# PCB_Mega.net
KiCad netlist of a schematic drawn in EAGLE
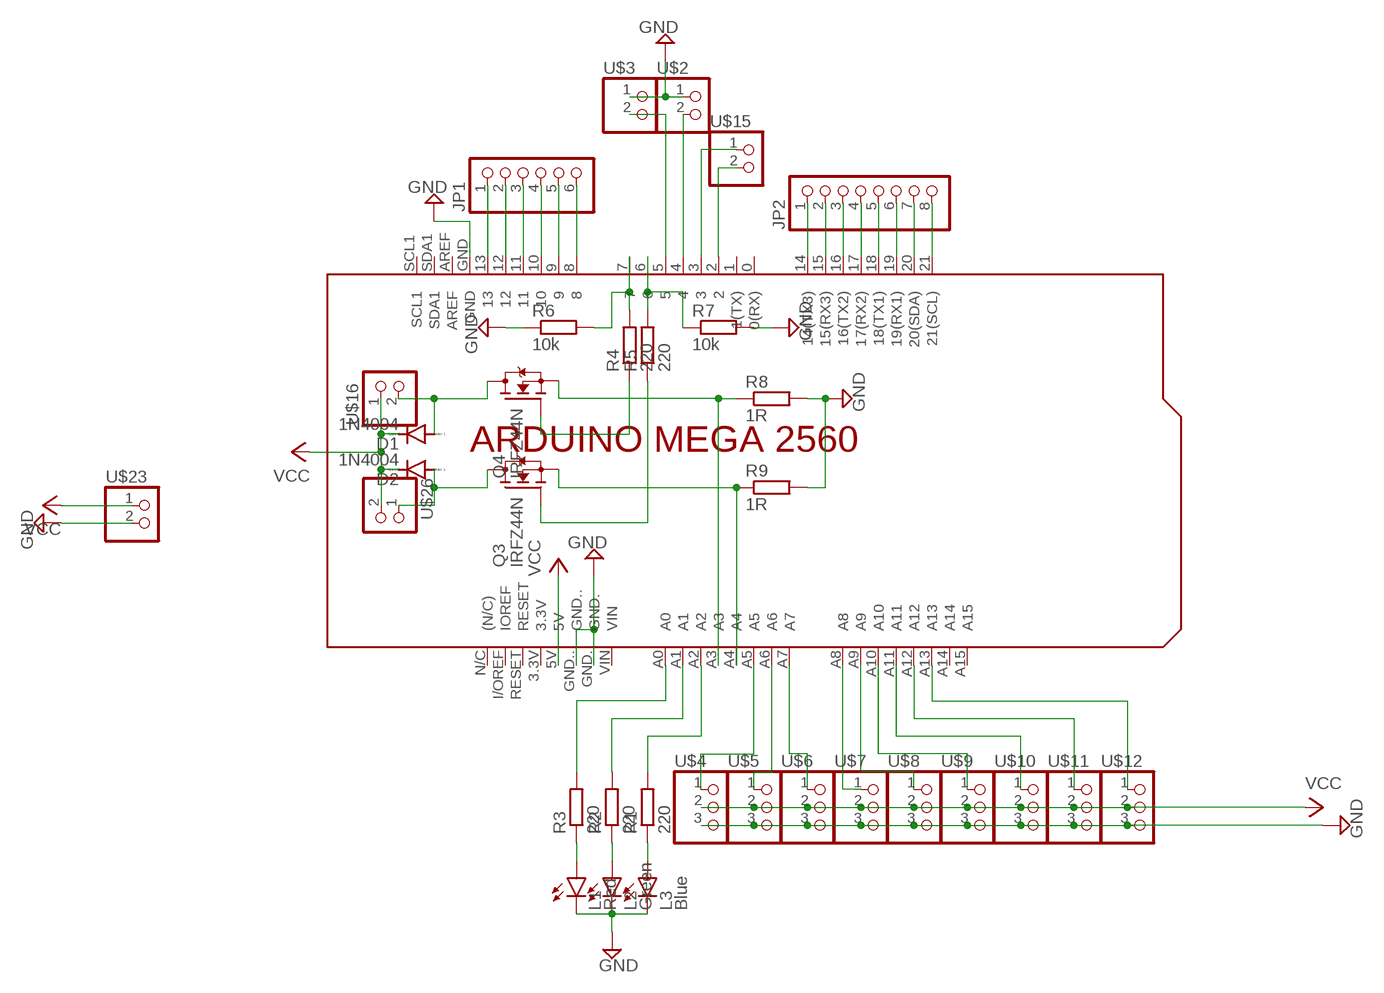
[diagram p0: schematic, sheet 1]

(export (version "E")
  (design (tool "Eeschema 10.0.6"))
  (components
    (comp (ref "D1")
      (value "1N4004")
      (footprint "eagle-import:DO41-10")
      (libsource (lib "eagle-import") (part "1N4004"))
    )
    (comp (ref "D2")
      (value "1N4004")
      (footprint "eagle-import:DO41-10")
      (libsource (lib "eagle-import") (part "1N4004"))
    )
    (comp (ref "JP1")
      (value "PINHD-1X6")
      (footprint "eagle-import:1X06")
      (libsource (lib "eagle-import") (part "PINHD-1X6"))
    )
    (comp (ref "JP2")
      (value "PINHD-1X8")
      (footprint "eagle-import:1X08")
      (libsource (lib "eagle-import") (part "PINHD-1X8"))
    )
    (comp (ref "L1")
      (value "Red")
      (footprint "eagle-import:LED3MM")
      (libsource (lib "eagle-import") (part "LED3MM"))
    )
    (comp (ref "L2")
      (value "Green")
      (footprint "eagle-import:LED3MM")
      (libsource (lib "eagle-import") (part "LED3MM"))
    )
    (comp (ref "L3")
      (value "Blue")
      (footprint "eagle-import:LED3MM")
      (libsource (lib "eagle-import") (part "LED3MM"))
    )
    (comp (ref "Q3")
      (value "IRFZ44N")
      (footprint "eagle-import:TO220V")
      (libsource (lib "eagle-import") (part "IRFZ44N"))
    )
    (comp (ref "Q4")
      (value "IRFZ44N")
      (footprint "eagle-import:TO220V")
      (libsource (lib "eagle-import") (part "IRFZ44N"))
    )
    (comp (ref "R1")
      (value "220")
      (footprint "eagle-import:0207_7-OFFSET")
      (libsource (lib "eagle-import") (part "RESISTOR_1/4WOFFSET"))
    )
    (comp (ref "R2")
      (value "220")
      (footprint "eagle-import:0207_7-OFFSET")
      (libsource (lib "eagle-import") (part "RESISTOR_1/4WOFFSET"))
    )
    (comp (ref "R3")
      (value "220")
      (footprint "eagle-import:0207_7-OFFSET")
      (libsource (lib "eagle-import") (part "RESISTOR_1/4WOFFSET"))
    )
    (comp (ref "R4")
      (value "220")
      (footprint "eagle-import:0207_7-OFFSET")
      (libsource (lib "eagle-import") (part "RESISTOR_1/4WOFFSET"))
    )
    (comp (ref "R5")
      (value "220")
      (footprint "eagle-import:0207_7-OFFSET")
      (libsource (lib "eagle-import") (part "RESISTOR_1/4WOFFSET"))
    )
    (comp (ref "R6")
      (value "10k")
      (footprint "eagle-import:0207_7-OFFSET")
      (libsource (lib "eagle-import") (part "RESISTOR_1/4WOFFSET"))
    )
    (comp (ref "R7")
      (value "10k")
      (footprint "eagle-import:0207_7-OFFSET")
      (libsource (lib "eagle-import") (part "RESISTOR_1/4WOFFSET"))
    )
    (comp (ref "R8")
      (value "1R")
      (footprint "eagle-import:10_28-90")
      (libsource (lib "eagle-import") (part "RESISTOR_5W90PAD"))
    )
    (comp (ref "R9")
      (value "1R")
      (footprint "eagle-import:10_28-90")
      (libsource (lib "eagle-import") (part "RESISTOR_5W90PAD"))
    )
    (comp (ref "U$1")
      (value "ARDUINO_MEGA2560_SHIELD_NO_LOWER")
      (footprint "eagle-import:ARDUINO_MEGA2560_SHIELD_NO_LOWER")
      (libsource (lib "eagle-import") (part "ARDUINO_MEGA2560_SHIELD_NO_LOWER"))
    )
    (comp (ref "U$2")
      (value "PINHD-1X2")
      (footprint "eagle-import:1X02")
      (libsource (lib "eagle-import") (part "PINHD-1X2"))
    )
    (comp (ref "U$3")
      (value "PINHD-1X2")
      (footprint "eagle-import:1X02")
      (libsource (lib "eagle-import") (part "PINHD-1X2"))
    )
    (comp (ref "U$4")
      (value "PINHD-1X3")
      (footprint "eagle-import:1X03")
      (libsource (lib "eagle-import") (part "PINHD-1X3"))
    )
    (comp (ref "U$5")
      (value "PINHD-1X3")
      (footprint "eagle-import:1X03")
      (libsource (lib "eagle-import") (part "PINHD-1X3"))
    )
    (comp (ref "U$6")
      (value "PINHD-1X3")
      (footprint "eagle-import:1X03")
      (libsource (lib "eagle-import") (part "PINHD-1X3"))
    )
    (comp (ref "U$7")
      (value "PINHD-1X3")
      (footprint "eagle-import:1X03")
      (libsource (lib "eagle-import") (part "PINHD-1X3"))
    )
    (comp (ref "U$8")
      (value "PINHD-1X3")
      (footprint "eagle-import:1X03")
      (libsource (lib "eagle-import") (part "PINHD-1X3"))
    )
    (comp (ref "U$9")
      (value "PINHD-1X3")
      (footprint "eagle-import:1X03")
      (libsource (lib "eagle-import") (part "PINHD-1X3"))
    )
    (comp (ref "U$10")
      (value "PINHD-1X3")
      (footprint "eagle-import:1X03")
      (libsource (lib "eagle-import") (part "PINHD-1X3"))
    )
    (comp (ref "U$11")
      (value "PINHD-1X3")
      (footprint "eagle-import:1X03")
      (libsource (lib "eagle-import") (part "PINHD-1X3"))
    )
    (comp (ref "U$12")
      (value "PINHD-1X3")
      (footprint "eagle-import:1X03")
      (libsource (lib "eagle-import") (part "PINHD-1X3"))
    )
    (comp (ref "U$15")
      (value "PINHD-1X2")
      (footprint "eagle-import:1X02")
      (libsource (lib "eagle-import") (part "PINHD-1X2"))
    )
    (comp (ref "U$16")
      (value "TERMINALBLOCK_1X2-5.0MM")
      (footprint "eagle-import:TERMINALBLOCK_1X2-5.0MM")
      (libsource (lib "eagle-import") (part "TERMINALBLOCK_1X2-5.0MM"))
    )
    (comp (ref "U$23")
      (value "TERMINALBLOCK_1X2-5.0MM")
      (footprint "eagle-import:TERMINALBLOCK_1X2-5.0MM")
      (libsource (lib "eagle-import") (part "TERMINALBLOCK_1X2-5.0MM"))
    )
    (comp (ref "U$26")
      (value "TERMINALBLOCK_1X2-5.0MM")
      (footprint "eagle-import:TERMINALBLOCK_1X2-5.0MM")
      (libsource (lib "eagle-import") (part "TERMINALBLOCK_1X2-5.0MM"))
    )
  )
  (nets
    (net (code "1") (name "GND") (class "Default")
      (node (ref "L1") (pin "K") (pinfunction "C_K") (pintype "passive"))
      (node (ref "L2") (pin "K") (pinfunction "C_K") (pintype "passive"))
      (node (ref "L3") (pin "K") (pinfunction "C_K") (pintype "passive"))
      (node (ref "R6") (pin "1") (pinfunction "1_1") (pintype "passive"))
      (node (ref "R7") (pin "2") (pinfunction "2_2") (pintype "passive"))
      (node (ref "R8") (pin "P$2") (pinfunction "2_P$2") (pintype "passive"))
      (node (ref "R9") (pin "P$2") (pinfunction "2_P$2") (pintype "passive"))
      (node (ref "U$1") (pin "GND") (pinfunction "GND_GND") (pintype "bidirectional"))
      (node (ref "U$1") (pin "GND.") (pinfunction "GND._GND.") (pintype "bidirectional"))
      (node (ref "U$1") (pin "GND..") (pinfunction "GND.._GND..") (pintype "bidirectional"))
      (node (ref "U$10") (pin "3") (pinfunction "3_3") (pintype "passive"))
      (node (ref "U$11") (pin "3") (pinfunction "3_3") (pintype "passive"))
      (node (ref "U$12") (pin "3") (pinfunction "3_3") (pintype "passive"))
      (node (ref "U$2") (pin "1") (pinfunction "1_1") (pintype "passive"))
      (node (ref "U$23") (pin "2") (pinfunction "2_2") (pintype "passive"))
      (node (ref "U$3") (pin "1") (pinfunction "1_1") (pintype "passive"))
      (node (ref "U$4") (pin "3") (pinfunction "3_3") (pintype "passive"))
      (node (ref "U$5") (pin "3") (pinfunction "3_3") (pintype "passive"))
      (node (ref "U$6") (pin "3") (pinfunction "3_3") (pintype "passive"))
      (node (ref "U$7") (pin "3") (pinfunction "3_3") (pintype "passive"))
      (node (ref "U$8") (pin "3") (pinfunction "3_3") (pintype "passive"))
      (node (ref "U$9") (pin "3") (pinfunction "3_3") (pintype "passive"))
    )
    (net (code "2") (name "Net-(JP1-Pad1)") (class "Default")
      (node (ref "JP1") (pin "1") (pinfunction "1_1") (pintype "passive"))
      (node (ref "U$1") (pin "13") (pinfunction "13_13") (pintype "bidirectional"))
    )
    (net (code "3") (name "Net-(JP1-Pad2)") (class "Default")
      (node (ref "JP1") (pin "2") (pinfunction "2_2") (pintype "passive"))
      (node (ref "U$1") (pin "12") (pinfunction "12_12") (pintype "bidirectional"))
    )
    (net (code "4") (name "Net-(JP1-Pad3)") (class "Default")
      (node (ref "JP1") (pin "3") (pinfunction "3_3") (pintype "passive"))
      (node (ref "U$1") (pin "11") (pinfunction "11_11") (pintype "bidirectional"))
    )
    (net (code "5") (name "Net-(JP1-Pad4)") (class "Default")
      (node (ref "JP1") (pin "4") (pinfunction "4_4") (pintype "passive"))
      (node (ref "U$1") (pin "10") (pinfunction "10_10") (pintype "bidirectional"))
    )
    (net (code "6") (name "Net-(JP1-Pad5)") (class "Default")
      (node (ref "JP1") (pin "5") (pinfunction "5_5") (pintype "passive"))
      (node (ref "U$1") (pin "9") (pinfunction "9_9") (pintype "bidirectional"))
    )
    (net (code "7") (name "Net-(JP1-Pad6)") (class "Default")
      (node (ref "JP1") (pin "6") (pinfunction "6_6") (pintype "passive"))
      (node (ref "U$1") (pin "8") (pinfunction "8_8") (pintype "bidirectional"))
    )
    (net (code "8") (name "Net-(L1-PadA)") (class "Default")
      (node (ref "L1") (pin "A") (pinfunction "A_A") (pintype "passive"))
      (node (ref "R3") (pin "1") (pinfunction "1_1") (pintype "passive"))
    )
    (net (code "9") (name "Net-(L2-PadA)") (class "Default")
      (node (ref "L2") (pin "A") (pinfunction "A_A") (pintype "passive"))
      (node (ref "R2") (pin "1") (pinfunction "1_1") (pintype "passive"))
    )
    (net (code "10") (name "Net-(L3-PadA)") (class "Default")
      (node (ref "L3") (pin "A") (pinfunction "A_A") (pintype "passive"))
      (node (ref "R1") (pin "1") (pinfunction "1_1") (pintype "passive"))
    )
    (net (code "11") (name "Net-(Q3-D)") (class "Default")
      (node (ref "D2") (pin "A") (pinfunction "A_A") (pintype "passive"))
      (node (ref "Q3") (pin "2") (pinfunction "D_2") (pintype "passive"))
      (node (ref "U$26") (pin "1") (pinfunction "1_1") (pintype "passive"))
    )
    (net (code "12") (name "Net-(Q3-G)") (class "Default")
      (node (ref "Q3") (pin "1") (pinfunction "G_1") (pintype "passive"))
      (node (ref "R5") (pin "1") (pinfunction "1_1") (pintype "passive"))
    )
    (net (code "13") (name "Net-(Q3-S)") (class "Default")
      (node (ref "Q3") (pin "3") (pinfunction "S_3") (pintype "passive"))
      (node (ref "R9") (pin "P$1") (pinfunction "1_P$1") (pintype "passive"))
      (node (ref "U$1") (pin "A4") (pinfunction "A4_A4") (pintype "bidirectional"))
    )
    (net (code "14") (name "Net-(Q4-D)") (class "Default")
      (node (ref "D1") (pin "A") (pinfunction "A_A") (pintype "passive"))
      (node (ref "Q4") (pin "2") (pinfunction "D_2") (pintype "passive"))
      (node (ref "U$16") (pin "2") (pinfunction "2_2") (pintype "passive"))
    )
    (net (code "15") (name "Net-(Q4-G)") (class "Default")
      (node (ref "Q4") (pin "1") (pinfunction "G_1") (pintype "passive"))
      (node (ref "R4") (pin "1") (pinfunction "1_1") (pintype "passive"))
    )
    (net (code "16") (name "Net-(Q4-S)") (class "Default")
      (node (ref "Q4") (pin "3") (pinfunction "S_3") (pintype "passive"))
      (node (ref "R8") (pin "P$1") (pinfunction "1_P$1") (pintype "passive"))
      (node (ref "U$1") (pin "A3") (pinfunction "A3_A3") (pintype "bidirectional"))
    )
    (net (code "17") (name "Net-(R1-Pad2)") (class "Default")
      (node (ref "R1") (pin "2") (pinfunction "2_2") (pintype "passive"))
      (node (ref "U$1") (pin "A2") (pinfunction "A2_A2") (pintype "bidirectional"))
    )
    (net (code "18") (name "Net-(R2-Pad2)") (class "Default")
      (node (ref "R2") (pin "2") (pinfunction "2_2") (pintype "passive"))
      (node (ref "U$1") (pin "A1") (pinfunction "A1_A1") (pintype "bidirectional"))
    )
    (net (code "19") (name "Net-(R3-Pad2)") (class "Default")
      (node (ref "R3") (pin "2") (pinfunction "2_2") (pintype "passive"))
      (node (ref "U$1") (pin "A0") (pinfunction "A0_A0") (pintype "bidirectional"))
    )
    (net (code "20") (name "Net-(R4-Pad2)") (class "Default")
      (node (ref "R4") (pin "2") (pinfunction "2_2") (pintype "passive"))
      (node (ref "R6") (pin "2") (pinfunction "2_2") (pintype "passive"))
      (node (ref "U$1") (pin "7") (pinfunction "7_7") (pintype "bidirectional"))
    )
    (net (code "21") (name "Net-(R5-Pad2)") (class "Default")
      (node (ref "R5") (pin "2") (pinfunction "2_2") (pintype "passive"))
      (node (ref "R7") (pin "1") (pinfunction "1_1") (pintype "passive"))
      (node (ref "U$1") (pin "6") (pinfunction "6_6") (pintype "bidirectional"))
    )
    (net (code "22") (name "Net-(U$1-14(TX3))") (class "Default")
      (node (ref "JP2") (pin "1") (pinfunction "1_1") (pintype "passive"))
      (node (ref "U$1") (pin "14") (pinfunction "14(TX3)_14") (pintype "bidirectional"))
    )
    (net (code "23") (name "Net-(U$1-15(RX3))") (class "Default")
      (node (ref "JP2") (pin "2") (pinfunction "2_2") (pintype "passive"))
      (node (ref "U$1") (pin "15") (pinfunction "15(RX3)_15") (pintype "bidirectional"))
    )
    (net (code "24") (name "Net-(U$1-16(TX2))") (class "Default")
      (node (ref "JP2") (pin "3") (pinfunction "3_3") (pintype "passive"))
      (node (ref "U$1") (pin "16") (pinfunction "16(TX2)_16") (pintype "bidirectional"))
    )
    (net (code "25") (name "Net-(U$1-17(RX2))") (class "Default")
      (node (ref "JP2") (pin "4") (pinfunction "4_4") (pintype "passive"))
      (node (ref "U$1") (pin "17") (pinfunction "17(RX2)_17") (pintype "bidirectional"))
    )
    (net (code "26") (name "Net-(U$1-18(TX1))") (class "Default")
      (node (ref "JP2") (pin "5") (pinfunction "5_5") (pintype "passive"))
      (node (ref "U$1") (pin "18") (pinfunction "18(TX1)_18") (pintype "bidirectional"))
    )
    (net (code "27") (name "Net-(U$1-19(RX1))") (class "Default")
      (node (ref "JP2") (pin "6") (pinfunction "6_6") (pintype "passive"))
      (node (ref "U$1") (pin "19") (pinfunction "19(RX1)_19") (pintype "bidirectional"))
    )
    (net (code "28") (name "Net-(U$1-20(SDA))") (class "Default")
      (node (ref "JP2") (pin "7") (pinfunction "7_7") (pintype "passive"))
      (node (ref "U$1") (pin "20") (pinfunction "20(SDA)_20") (pintype "bidirectional"))
    )
    (net (code "29") (name "Net-(U$1-21(SCL))") (class "Default")
      (node (ref "JP2") (pin "8") (pinfunction "8_8") (pintype "passive"))
      (node (ref "U$1") (pin "21") (pinfunction "21(SCL)_21") (pintype "bidirectional"))
    )
    (net (code "30") (name "Net-(U$1-Pad2)") (class "Default")
      (node (ref "U$1") (pin "2") (pinfunction "2_2") (pintype "bidirectional"))
      (node (ref "U$15") (pin "2") (pinfunction "2_2") (pintype "passive"))
    )
    (net (code "31") (name "Net-(U$1-Pad3)") (class "Default")
      (node (ref "U$1") (pin "3") (pinfunction "3_3") (pintype "bidirectional"))
      (node (ref "U$15") (pin "1") (pinfunction "1_1") (pintype "passive"))
    )
    (net (code "32") (name "Net-(U$1-Pad4)") (class "Default")
      (node (ref "U$1") (pin "4") (pinfunction "4_4") (pintype "bidirectional"))
      (node (ref "U$2") (pin "2") (pinfunction "2_2") (pintype "passive"))
    )
    (net (code "33") (name "Net-(U$1-Pad5)") (class "Default")
      (node (ref "U$1") (pin "5") (pinfunction "5_5") (pintype "bidirectional"))
      (node (ref "U$3") (pin "2") (pinfunction "2_2") (pintype "passive"))
    )
    (net (code "34") (name "Net-(U$1-PadA5)") (class "Default")
      (node (ref "U$1") (pin "A5") (pinfunction "A5_A5") (pintype "bidirectional"))
      (node (ref "U$4") (pin "1") (pinfunction "1_1") (pintype "passive"))
    )
    (net (code "35") (name "Net-(U$1-PadA6)") (class "Default")
      (node (ref "U$1") (pin "A6") (pinfunction "A6_A6") (pintype "bidirectional"))
      (node (ref "U$5") (pin "1") (pinfunction "1_1") (pintype "passive"))
    )
    (net (code "36") (name "Net-(U$1-PadA7)") (class "Default")
      (node (ref "U$1") (pin "A7") (pinfunction "A7_A7") (pintype "bidirectional"))
      (node (ref "U$6") (pin "1") (pinfunction "1_1") (pintype "passive"))
    )
    (net (code "37") (name "Net-(U$1-PadA8)") (class "Default")
      (node (ref "U$1") (pin "A8") (pinfunction "A8_A8") (pintype "bidirectional"))
      (node (ref "U$7") (pin "1") (pinfunction "1_1") (pintype "passive"))
    )
    (net (code "38") (name "Net-(U$1-PadA9)") (class "Default")
      (node (ref "U$1") (pin "A9") (pinfunction "A9_A9") (pintype "bidirectional"))
      (node (ref "U$8") (pin "1") (pinfunction "1_1") (pintype "passive"))
    )
    (net (code "39") (name "Net-(U$1-PadA10)") (class "Default")
      (node (ref "U$1") (pin "A10") (pinfunction "A10_A10") (pintype "bidirectional"))
      (node (ref "U$9") (pin "1") (pinfunction "1_1") (pintype "passive"))
    )
    (net (code "40") (name "Net-(U$1-PadA11)") (class "Default")
      (node (ref "U$1") (pin "A11") (pinfunction "A11_A11") (pintype "bidirectional"))
      (node (ref "U$10") (pin "1") (pinfunction "1_1") (pintype "passive"))
    )
    (net (code "41") (name "Net-(U$1-PadA12)") (class "Default")
      (node (ref "U$1") (pin "A12") (pinfunction "A12_A12") (pintype "bidirectional"))
      (node (ref "U$11") (pin "1") (pinfunction "1_1") (pintype "passive"))
    )
    (net (code "42") (name "Net-(U$1-PadA13)") (class "Default")
      (node (ref "U$1") (pin "A13") (pinfunction "A13_A13") (pintype "bidirectional"))
      (node (ref "U$12") (pin "1") (pinfunction "1_1") (pintype "passive"))
    )
    (net (code "43") (name "VCC") (class "Default")
      (node (ref "D1") (pin "C") (pinfunction "C_C") (pintype "passive"))
      (node (ref "D2") (pin "C") (pinfunction "C_C") (pintype "passive"))
      (node (ref "U$1") (pin "5V") (pinfunction "5V_5V") (pintype "bidirectional"))
      (node (ref "U$10") (pin "2") (pinfunction "2_2") (pintype "passive"))
      (node (ref "U$11") (pin "2") (pinfunction "2_2") (pintype "passive"))
      (node (ref "U$12") (pin "2") (pinfunction "2_2") (pintype "passive"))
      (node (ref "U$16") (pin "1") (pinfunction "1_1") (pintype "passive"))
      (node (ref "U$23") (pin "1") (pinfunction "1_1") (pintype "passive"))
      (node (ref "U$26") (pin "2") (pinfunction "2_2") (pintype "passive"))
      (node (ref "U$4") (pin "2") (pinfunction "2_2") (pintype "passive"))
      (node (ref "U$5") (pin "2") (pinfunction "2_2") (pintype "passive"))
      (node (ref "U$6") (pin "2") (pinfunction "2_2") (pintype "passive"))
      (node (ref "U$7") (pin "2") (pinfunction "2_2") (pintype "passive"))
      (node (ref "U$8") (pin "2") (pinfunction "2_2") (pintype "passive"))
      (node (ref "U$9") (pin "2") (pinfunction "2_2") (pintype "passive"))
    )
    (net (code "44") (name "unconnected-(U$1-(N{slash}C)-PadN{slash}C)") (class "Default")
      (node (ref "U$1") (pin "N/C") (pinfunction "(N/C)_N/C") (pintype "bidirectional"))
    )
    (net (code "45") (name "unconnected-(U$1-0(RX)-Pad0)") (class "Default")
      (node (ref "U$1") (pin "0") (pinfunction "0(RX)_0") (pintype "bidirectional"))
    )
    (net (code "46") (name "unconnected-(U$1-1(TX)-Pad1)") (class "Default")
      (node (ref "U$1") (pin "1") (pinfunction "1(TX)_1") (pintype "bidirectional"))
    )
    (net (code "47") (name "unconnected-(U$1-IOREF-PadI{slash}OREF)") (class "Default")
      (node (ref "U$1") (pin "I/OREF") (pinfunction "IOREF_I/OREF") (pintype "bidirectional"))
    )
    (net (code "48") (name "unconnected-(U$1-Pad3.3V)") (class "Default")
      (node (ref "U$1") (pin "3.3V") (pinfunction "3.3V_3.3V") (pintype "bidirectional"))
    )
    (net (code "49") (name "unconnected-(U$1-PadA14)") (class "Default")
      (node (ref "U$1") (pin "A14") (pinfunction "A14_A14") (pintype "bidirectional"))
    )
    (net (code "50") (name "unconnected-(U$1-PadA15)") (class "Default")
      (node (ref "U$1") (pin "A15") (pinfunction "A15_A15") (pintype "bidirectional"))
    )
    (net (code "51") (name "unconnected-(U$1-PadAREF)") (class "Default")
      (node (ref "U$1") (pin "AREF") (pinfunction "AREF_AREF") (pintype "bidirectional"))
    )
    (net (code "52") (name "unconnected-(U$1-PadRESET)") (class "Default")
      (node (ref "U$1") (pin "RESET") (pinfunction "RESET_RESET") (pintype "bidirectional"))
    )
    (net (code "53") (name "unconnected-(U$1-PadSCL1)") (class "Default")
      (node (ref "U$1") (pin "SCL1") (pinfunction "SCL1_SCL1") (pintype "bidirectional"))
    )
    (net (code "54") (name "unconnected-(U$1-PadSDA1)") (class "Default")
      (node (ref "U$1") (pin "SDA1") (pinfunction "SDA1_SDA1") (pintype "bidirectional"))
    )
    (net (code "55") (name "unconnected-(U$1-PadVIN)") (class "Default")
      (node (ref "U$1") (pin "VIN") (pinfunction "VIN_VIN") (pintype "bidirectional"))
    )
  )
)
